# Power_MPU.net
KiCad netlist of a schematic drawn in Altium Designer
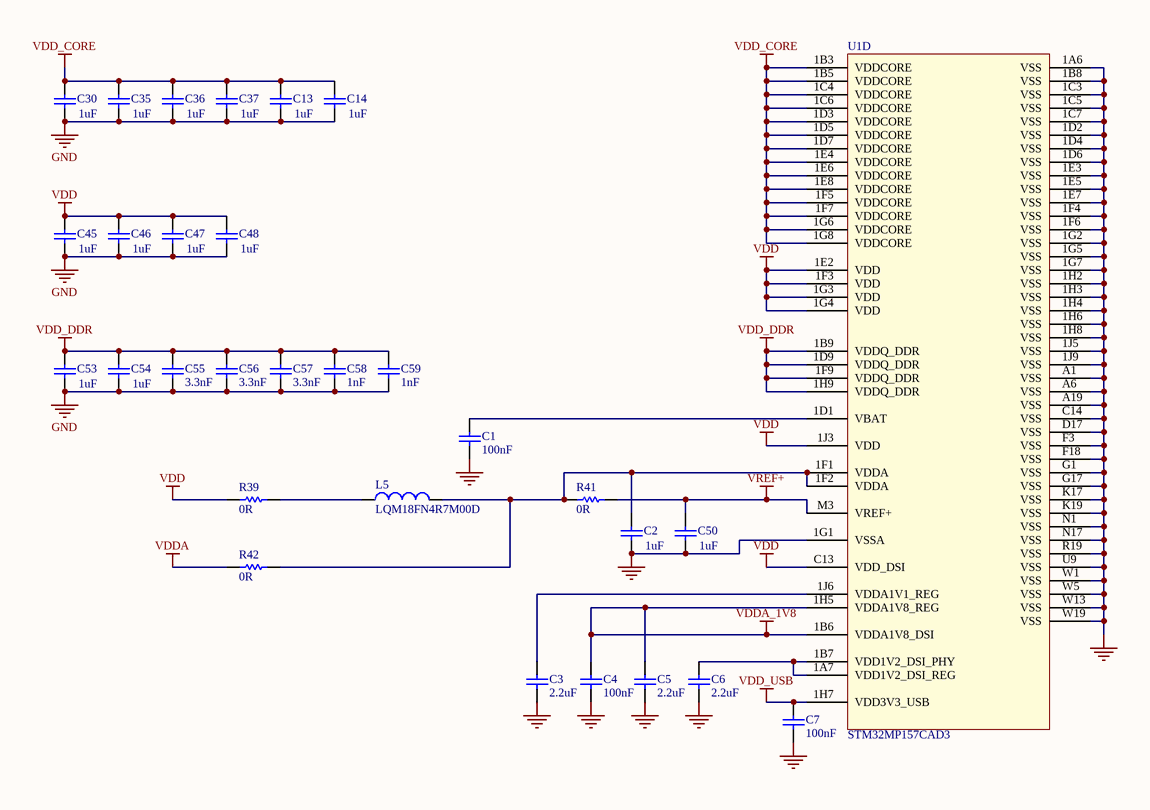
[diagram p0: Power_MPU.SchDoc]

(export (version "E")
  (design (tool "Eeschema 10.0.6"))
  (components
    (comp (ref "C1")
      (value "100nF")
      (footprint "C0402")
      (description "Capacitor, MLCC, 100nF, 16V, X7R, 10%, 0402, T=0.5mm")
      (fields
        (field (name "INTERNAL_PART_NUMBER") "MCD-00006")
        (field (name "MANUFACTURER_PART_NUMBER") "CC0402KRX7R7BB104")
        (field (name "PROVIDED_BY") "SUBCO")
      )
      (libsource (lib "MCD_PARTS_database") (part "Capacitor"))
    )
    (comp (ref "C2")
      (value "1uF")
      (footprint "C0402")
      (description "Capacitor, MLCC, 1uF, 6V3, X5R, 10%, 0402, T=0,5mm")
      (fields
        (field (name "INTERNAL_PART_NUMBER") "MCD-00095")
        (field (name "MANUFACTURER_PART_NUMBER") "GRM155R61E105KA12")
        (field (name "PROVIDED_BY") "SUBCO")
      )
      (libsource (lib "MCD_PARTS_database") (part "Capacitor"))
    )
    (comp (ref "C3")
      (value "2.2uF")
      (footprint "C0402")
      (description "Capacitor,MLCC,2.2uF,6V3,X5R,10%,0402,T=0.5")
      (fields
        (field (name "INTERNAL_PART_NUMBER") "MCD-01823")
        (field (name "MANUFACTURER_PART_NUMBER") "GRM155R60J225KE95D")
        (field (name "PROVIDED_BY") "SUBCO")
      )
      (libsource (lib "MCD_PARTS_database") (part "Capacitor"))
    )
    (comp (ref "C4")
      (value "100nF")
      (footprint "C0402")
      (description "Capacitor, MLCC, 100nF, 16V, X7R, 10%, 0402, T=0.5mm")
      (fields
        (field (name "INTERNAL_PART_NUMBER") "MCD-00006")
        (field (name "MANUFACTURER_PART_NUMBER") "CC0402KRX7R7BB104")
        (field (name "PROVIDED_BY") "SUBCO")
      )
      (libsource (lib "MCD_PARTS_database") (part "Capacitor"))
    )
    (comp (ref "C5")
      (value "2.2uF")
      (footprint "C0402")
      (description "Capacitor,MLCC,2.2uF,6V3,X5R,10%,0402,T=0.5")
      (fields
        (field (name "INTERNAL_PART_NUMBER") "MCD-01823")
        (field (name "MANUFACTURER_PART_NUMBER") "GRM155R60J225KE95D")
        (field (name "PROVIDED_BY") "SUBCO")
      )
      (libsource (lib "MCD_PARTS_database") (part "Capacitor"))
    )
    (comp (ref "C6")
      (value "2.2uF")
      (footprint "C0402")
      (description "Capacitor,MLCC,2.2uF,6V3,X5R,10%,0402,T=0.5")
      (fields
        (field (name "INTERNAL_PART_NUMBER") "MCD-01823")
        (field (name "MANUFACTURER_PART_NUMBER") "GRM155R60J225KE95D")
        (field (name "PROVIDED_BY") "SUBCO")
      )
      (libsource (lib "MCD_PARTS_database") (part "Capacitor"))
    )
    (comp (ref "C7")
      (value "100nF")
      (footprint "C0402")
      (description "Capacitor, MLCC, 100nF, 16V, X7R, 10%, 0402, T=0.5mm")
      (fields
        (field (name "INTERNAL_PART_NUMBER") "MCD-00006")
        (field (name "MANUFACTURER_PART_NUMBER") "CC0402KRX7R7BB104")
        (field (name "PROVIDED_BY") "SUBCO")
      )
      (libsource (lib "MCD_PARTS_database") (part "Capacitor"))
    )
    (comp (ref "C13")
      (value "1uF")
      (footprint "C0402")
      (description "Capacitor, MLCC, 1uF, 6V3, X5R, 10%, 0402, T=0,5mm")
      (fields
        (field (name "INTERNAL_PART_NUMBER") "MCD-00095")
        (field (name "MANUFACTURER_PART_NUMBER") "GRM155R61E105KA12")
        (field (name "PROVIDED_BY") "SUBCO")
      )
      (libsource (lib "MCD_PARTS_database") (part "Capacitor"))
    )
    (comp (ref "C14")
      (value "1uF")
      (footprint "C0402")
      (description "Capacitor, MLCC, 1uF, 6V3, X5R, 10%, 0402, T=0,5mm")
      (fields
        (field (name "INTERNAL_PART_NUMBER") "MCD-00095")
        (field (name "MANUFACTURER_PART_NUMBER") "GRM155R61E105KA12")
        (field (name "PROVIDED_BY") "SUBCO")
      )
      (libsource (lib "MCD_PARTS_database") (part "Capacitor"))
    )
    (comp (ref "C30")
      (value "1uF")
      (footprint "C0402")
      (description "Capacitor, MLCC, 1uF, 6V3, X5R, 10%, 0402, T=0,5mm")
      (fields
        (field (name "INTERNAL_PART_NUMBER") "MCD-00095")
        (field (name "MANUFACTURER_PART_NUMBER") "GRM155R61E105KA12")
        (field (name "PROVIDED_BY") "SUBCO")
      )
      (libsource (lib "MCD_PARTS_database") (part "Capacitor"))
    )
    (comp (ref "C35")
      (value "1uF")
      (footprint "C0402")
      (description "Capacitor, MLCC, 1uF, 6V3, X5R, 10%, 0402, T=0,5mm")
      (fields
        (field (name "INTERNAL_PART_NUMBER") "MCD-00095")
        (field (name "MANUFACTURER_PART_NUMBER") "GRM155R61E105KA12")
        (field (name "PROVIDED_BY") "SUBCO")
      )
      (libsource (lib "MCD_PARTS_database") (part "Capacitor"))
    )
    (comp (ref "C36")
      (value "1uF")
      (footprint "C0402")
      (description "Capacitor, MLCC, 1uF, 6V3, X5R, 10%, 0402, T=0,5mm")
      (fields
        (field (name "INTERNAL_PART_NUMBER") "MCD-00095")
        (field (name "MANUFACTURER_PART_NUMBER") "GRM155R61E105KA12")
        (field (name "PROVIDED_BY") "SUBCO")
      )
      (libsource (lib "MCD_PARTS_database") (part "Capacitor"))
    )
    (comp (ref "C37")
      (value "1uF")
      (footprint "C0402")
      (description "Capacitor, MLCC, 1uF, 6V3, X5R, 10%, 0402, T=0,5mm")
      (fields
        (field (name "INTERNAL_PART_NUMBER") "MCD-00095")
        (field (name "MANUFACTURER_PART_NUMBER") "GRM155R61E105KA12")
        (field (name "PROVIDED_BY") "SUBCO")
      )
      (libsource (lib "MCD_PARTS_database") (part "Capacitor"))
    )
    (comp (ref "C45")
      (value "1uF")
      (footprint "C0402")
      (description "Capacitor, MLCC, 1uF, 6V3, X5R, 10%, 0402, T=0,5mm")
      (fields
        (field (name "INTERNAL_PART_NUMBER") "MCD-00095")
        (field (name "MANUFACTURER_PART_NUMBER") "GRM155R61E105KA12")
        (field (name "PROVIDED_BY") "SUBCO")
      )
      (libsource (lib "MCD_PARTS_database") (part "Capacitor"))
    )
    (comp (ref "C46")
      (value "1uF")
      (footprint "C0402")
      (description "Capacitor, MLCC, 1uF, 6V3, X5R, 10%, 0402, T=0,5mm")
      (fields
        (field (name "INTERNAL_PART_NUMBER") "MCD-00095")
        (field (name "MANUFACTURER_PART_NUMBER") "GRM155R61E105KA12")
        (field (name "PROVIDED_BY") "SUBCO")
      )
      (libsource (lib "MCD_PARTS_database") (part "Capacitor"))
    )
    (comp (ref "C47")
      (value "1uF")
      (footprint "C0402")
      (description "Capacitor, MLCC, 1uF, 6V3, X5R, 10%, 0402, T=0,5mm")
      (fields
        (field (name "INTERNAL_PART_NUMBER") "MCD-00095")
        (field (name "MANUFACTURER_PART_NUMBER") "GRM155R61E105KA12")
        (field (name "PROVIDED_BY") "SUBCO")
      )
      (libsource (lib "MCD_PARTS_database") (part "Capacitor"))
    )
    (comp (ref "C48")
      (value "1uF")
      (footprint "C0402")
      (description "Capacitor, MLCC, 1uF, 6V3, X5R, 10%, 0402, T=0,5mm")
      (fields
        (field (name "INTERNAL_PART_NUMBER") "MCD-00095")
        (field (name "MANUFACTURER_PART_NUMBER") "GRM155R61E105KA12")
        (field (name "PROVIDED_BY") "SUBCO")
      )
      (libsource (lib "MCD_PARTS_database") (part "Capacitor"))
    )
    (comp (ref "C50")
      (value "1uF")
      (footprint "C0402")
      (description "Capacitor, MLCC, 1uF, 6V3, X5R, 10%, 0402, T=0,5mm")
      (fields
        (field (name "INTERNAL_PART_NUMBER") "MCD-00095")
        (field (name "MANUFACTURER_PART_NUMBER") "GRM155R61E105KA12")
        (field (name "PROVIDED_BY") "SUBCO")
      )
      (libsource (lib "MCD_PARTS_database") (part "Capacitor"))
    )
    (comp (ref "C53")
      (value "1uF")
      (footprint "C0402")
      (description "Capacitor, MLCC, 1uF, 6V3, X5R, 10%, 0402, T=0,5mm")
      (fields
        (field (name "INTERNAL_PART_NUMBER") "MCD-00095")
        (field (name "MANUFACTURER_PART_NUMBER") "GRM155R61E105KA12")
        (field (name "PROVIDED_BY") "SUBCO")
      )
      (libsource (lib "MCD_PARTS_database") (part "Capacitor"))
    )
    (comp (ref "C54")
      (value "1uF")
      (footprint "C0402")
      (description "Capacitor, MLCC, 1uF, 6V3, X5R, 10%, 0402, T=0,5mm")
      (fields
        (field (name "INTERNAL_PART_NUMBER") "MCD-00095")
        (field (name "MANUFACTURER_PART_NUMBER") "GRM155R61E105KA12")
        (field (name "PROVIDED_BY") "SUBCO")
      )
      (libsource (lib "MCD_PARTS_database") (part "Capacitor"))
    )
    (comp (ref "C55")
      (value "3.3nF")
      (footprint "C0402")
      (description "Capacitor, MLCC, 3.3nF, 16V, X7R, 10%, 0402, T=0.5mm")
      (fields
        (field (name "INTERNAL_PART_NUMBER") "MCD-01462")
        (field (name "MANUFACTURER_PART_NUMBER") "CC0402KRX7R7BB332")
        (field (name "PROVIDED_BY") "SUBCO")
      )
      (libsource (lib "MCD_PARTS_database") (part "Capacitor"))
    )
    (comp (ref "C56")
      (value "3.3nF")
      (footprint "C0402")
      (description "Capacitor, MLCC, 3.3nF, 16V, X7R, 10%, 0402, T=0.5mm")
      (fields
        (field (name "INTERNAL_PART_NUMBER") "MCD-01462")
        (field (name "MANUFACTURER_PART_NUMBER") "CC0402KRX7R7BB332")
        (field (name "PROVIDED_BY") "SUBCO")
      )
      (libsource (lib "MCD_PARTS_database") (part "Capacitor"))
    )
    (comp (ref "C57")
      (value "3.3nF")
      (footprint "C0402")
      (description "Capacitor, MLCC, 3.3nF, 16V, X7R, 10%, 0402, T=0.5mm")
      (fields
        (field (name "INTERNAL_PART_NUMBER") "MCD-01462")
        (field (name "MANUFACTURER_PART_NUMBER") "CC0402KRX7R7BB332")
        (field (name "PROVIDED_BY") "SUBCO")
      )
      (libsource (lib "MCD_PARTS_database") (part "Capacitor"))
    )
    (comp (ref "C58")
      (value "1nF")
      (footprint "C0402")
      (description "Capacitor, MLCC, 1nF, 16V, X7R, 10%, 0402, T=0.5mm")
      (fields
        (field (name "INTERNAL_PART_NUMBER") "MCD-00198")
        (field (name "MANUFACTURER_PART_NUMBER") "CC0402KRX7R7BB102")
        (field (name "PROVIDED_BY") "SUBCO")
      )
      (libsource (lib "MCD_PARTS_database") (part "Capacitor"))
    )
    (comp (ref "C59")
      (value "1nF")
      (footprint "C0402")
      (description "Capacitor, MLCC, 1nF, 16V, X7R, 10%, 0402, T=0.5mm")
      (fields
        (field (name "INTERNAL_PART_NUMBER") "MCD-00198")
        (field (name "MANUFACTURER_PART_NUMBER") "CC0402KRX7R7BB102")
        (field (name "PROVIDED_BY") "SUBCO")
      )
      (libsource (lib "MCD_PARTS_database") (part "Capacitor"))
    )
    (comp (ref "L5")
      (value "LQM18FN4R7M00D")
      (footprint "L0603_H0P8")
      (description "IND 4.7uH 20% 80mA 600mhom 0603")
      (fields
        (field (name "INTERNAL_PART_NUMBER") "MCD-01134")
        (field (name "MANUFACTURER") "MURATA")
        (field (name "PROVIDED_BY") "SUBCO")
      )
      (libsource (lib "MCD_PARTS_database") (part "LQM18FN4R7M00D"))
    )
    (comp (ref "R39")
      (value "0R")
      (footprint "R0402")
      (description "Resistor,0R,0402,5%,1/16W")
      (fields
        (field (name "INTERNAL_PART_NUMBER") "MCD-00052")
        (field (name "MANUFACTURER_PART_NUMBER") "RC0402JR-070RL")
        (field (name "PROVIDED_BY") "SUBCO")
      )
      (libsource (lib "MCD_PARTS_database") (part "Resistor"))
    )
    (comp (ref "R41")
      (value "0R")
      (footprint "R0402")
      (description "Resistor,0R,0402,5%,1/16W")
      (fields
        (field (name "INTERNAL_PART_NUMBER") "MCD-00052")
        (field (name "MANUFACTURER_PART_NUMBER") "RC0402JR-070RL")
        (field (name "PROVIDED_BY") "SUBCO")
      )
      (libsource (lib "MCD_PARTS_database") (part "Resistor"))
    )
    (comp (ref "R42")
      (value "0R")
      (footprint "R0402")
      (description "Resistor,0R,0402,5%,1/16W")
      (fields
        (field (name "INTERNAL_PART_NUMBER") "MCD-00052")
        (field (name "MANUFACTURER_PART_NUMBER") "RC0402JR-070RL")
        (field (name "PROVIDED_BY") "SUBCO")
      )
      (libsource (lib "MCD_PARTS_database") (part "Resistor"))
    )
    (comp (ref "U1")
      (value "STM32MP157CAD3")
      (footprint "ICC_TFBGA257_10X10_STM32MP157CAD3_P050-065")
      (description "MPU TFBGA10x10 secure boot+crypto")
      (fields
        (field (name "INTERNAL_PART_NUMBER") "MCD-01144")
        (field (name "MANUFACTURER") "STMICROELECTRONICS")
        (field (name "PROVIDED_BY") "SUBCO with ST control")
      )
      (libsource (lib "MCD_PARTS_database") (part "STM32MP157CAD3"))
    )
  )
  (nets
    (net (code "1") (name "GND") (class "Default")
      (node (ref "C1") (pin "1") (pinfunction "1_1") (pintype "passive"))
      (node (ref "C13") (pin "1") (pinfunction "1_1") (pintype "passive"))
      (node (ref "C14") (pin "1") (pinfunction "1_1") (pintype "passive"))
      (node (ref "C2") (pin "1") (pinfunction "1_1") (pintype "passive"))
      (node (ref "C3") (pin "1") (pinfunction "1_1") (pintype "passive"))
      (node (ref "C30") (pin "1") (pinfunction "1_1") (pintype "passive"))
      (node (ref "C35") (pin "1") (pinfunction "1_1") (pintype "passive"))
      (node (ref "C36") (pin "1") (pinfunction "1_1") (pintype "passive"))
      (node (ref "C37") (pin "1") (pinfunction "1_1") (pintype "passive"))
      (node (ref "C4") (pin "1") (pinfunction "1_1") (pintype "passive"))
      (node (ref "C45") (pin "1") (pinfunction "1_1") (pintype "passive"))
      (node (ref "C46") (pin "1") (pinfunction "1_1") (pintype "passive"))
      (node (ref "C47") (pin "1") (pinfunction "1_1") (pintype "passive"))
      (node (ref "C48") (pin "1") (pinfunction "1_1") (pintype "passive"))
      (node (ref "C5") (pin "1") (pinfunction "1_1") (pintype "passive"))
      (node (ref "C50") (pin "1") (pinfunction "1_1") (pintype "passive"))
      (node (ref "C53") (pin "1") (pinfunction "1_1") (pintype "passive"))
      (node (ref "C54") (pin "1") (pinfunction "1_1") (pintype "passive"))
      (node (ref "C55") (pin "1") (pinfunction "1_1") (pintype "passive"))
      (node (ref "C56") (pin "1") (pinfunction "1_1") (pintype "passive"))
      (node (ref "C57") (pin "1") (pinfunction "1_1") (pintype "passive"))
      (node (ref "C58") (pin "1") (pinfunction "1_1") (pintype "passive"))
      (node (ref "C59") (pin "1") (pinfunction "1_1") (pintype "passive"))
      (node (ref "C6") (pin "1") (pinfunction "1_1") (pintype "passive"))
      (node (ref "C7") (pin "1") (pinfunction "1_1") (pintype "passive"))
      (node (ref "U1") (pin "1A6") (pinfunction "VSS_1A6") (pintype "passive"))
      (node (ref "U1") (pin "1B8") (pinfunction "VSS_1B8") (pintype "passive"))
      (node (ref "U1") (pin "1C3") (pinfunction "VSS_1C3") (pintype "passive"))
      (node (ref "U1") (pin "1C5") (pinfunction "VSS_1C5") (pintype "passive"))
      (node (ref "U1") (pin "1C7") (pinfunction "VSS_1C7") (pintype "passive"))
      (node (ref "U1") (pin "1D2") (pinfunction "VSS_1D2") (pintype "passive"))
      (node (ref "U1") (pin "1D4") (pinfunction "VSS_1D4") (pintype "passive"))
      (node (ref "U1") (pin "1D6") (pinfunction "VSS_1D6") (pintype "passive"))
      (node (ref "U1") (pin "1E3") (pinfunction "VSS_1E3") (pintype "passive"))
      (node (ref "U1") (pin "1E5") (pinfunction "VSS_1E5") (pintype "passive"))
      (node (ref "U1") (pin "1E7") (pinfunction "VSS_1E7") (pintype "passive"))
      (node (ref "U1") (pin "1F4") (pinfunction "VSS_1F4") (pintype "passive"))
      (node (ref "U1") (pin "1F6") (pinfunction "VSS_1F6") (pintype "passive"))
      (node (ref "U1") (pin "1G1") (pinfunction "VSSA_1G1") (pintype "passive"))
      (node (ref "U1") (pin "1G2") (pinfunction "VSS_1G2") (pintype "passive"))
      (node (ref "U1") (pin "1G5") (pinfunction "VSS_1G5") (pintype "passive"))
      (node (ref "U1") (pin "1G7") (pinfunction "VSS_1G7") (pintype "passive"))
      (node (ref "U1") (pin "1H2") (pinfunction "VSS_1H2") (pintype "passive"))
      (node (ref "U1") (pin "1H3") (pinfunction "VSS_1H3") (pintype "passive"))
      (node (ref "U1") (pin "1H4") (pinfunction "VSS_1H4") (pintype "passive"))
      (node (ref "U1") (pin "1H6") (pinfunction "VSS_1H6") (pintype "passive"))
      (node (ref "U1") (pin "1H8") (pinfunction "VSS_1H8") (pintype "passive"))
      (node (ref "U1") (pin "1J5") (pinfunction "VSS_1J5") (pintype "passive"))
      (node (ref "U1") (pin "1J9") (pinfunction "VSS_1J9") (pintype "passive"))
      (node (ref "U1") (pin "A1") (pinfunction "VSS_A1") (pintype "passive"))
      (node (ref "U1") (pin "A19") (pinfunction "VSS_A19") (pintype "passive"))
      (node (ref "U1") (pin "A6") (pinfunction "VSS_A6") (pintype "passive"))
      (node (ref "U1") (pin "C14") (pinfunction "VSS_C14") (pintype "passive"))
      (node (ref "U1") (pin "D17") (pinfunction "VSS_D17") (pintype "passive"))
      (node (ref "U1") (pin "F18") (pinfunction "VSS_F18") (pintype "passive"))
      (node (ref "U1") (pin "F3") (pinfunction "VSS_F3") (pintype "passive"))
      (node (ref "U1") (pin "G1") (pinfunction "VSS_G1") (pintype "passive"))
      (node (ref "U1") (pin "G17") (pinfunction "VSS_G17") (pintype "passive"))
      (node (ref "U1") (pin "K17") (pinfunction "VSS_K17") (pintype "passive"))
      (node (ref "U1") (pin "K19") (pinfunction "VSS_K19") (pintype "passive"))
      (node (ref "U1") (pin "N1") (pinfunction "VSS_N1") (pintype "passive"))
      (node (ref "U1") (pin "N17") (pinfunction "VSS_N17") (pintype "passive"))
      (node (ref "U1") (pin "R19") (pinfunction "VSS_R19") (pintype "passive"))
      (node (ref "U1") (pin "U9") (pinfunction "VSS_U9") (pintype "passive"))
      (node (ref "U1") (pin "W1") (pinfunction "VSS_W1") (pintype "passive"))
      (node (ref "U1") (pin "W13") (pinfunction "VSS_W13") (pintype "passive"))
      (node (ref "U1") (pin "W19") (pinfunction "VSS_W19") (pintype "passive"))
      (node (ref "U1") (pin "W5") (pinfunction "VSS_W5") (pintype "passive"))
    )
    (net (code "2") (name "Net-(C2-Pad2)") (class "Default")
      (node (ref "C2") (pin "2") (pinfunction "2_2") (pintype "passive"))
      (node (ref "L5") (pin "2") (pinfunction "2_2") (pintype "passive"))
      (node (ref "R41") (pin "1") (pinfunction "1_1") (pintype "passive"))
      (node (ref "R42") (pin "2") (pinfunction "2_2") (pintype "passive"))
      (node (ref "U1") (pin "1F1") (pinfunction "VDDA_1F1") (pintype "passive"))
      (node (ref "U1") (pin "1F2") (pinfunction "VDDA_1F2") (pintype "passive"))
    )
    (net (code "3") (name "Net-(L5-Pad1)") (class "Default")
      (node (ref "L5") (pin "1") (pinfunction "1_1") (pintype "passive"))
      (node (ref "R39") (pin "2") (pinfunction "2_2") (pintype "passive"))
    )
    (net (code "4") (name "Net-(U1D-VBAT)") (class "Default")
      (node (ref "C1") (pin "2") (pinfunction "2_2") (pintype "passive"))
      (node (ref "U1") (pin "1D1") (pinfunction "VBAT_1D1") (pintype "passive"))
    )
    (net (code "5") (name "Net-(U1D-VDD1V2_DSI_PHY)") (class "Default")
      (node (ref "C6") (pin "2") (pinfunction "2_2") (pintype "passive"))
      (node (ref "U1") (pin "1A7") (pinfunction "VDD1V2_DSI_REG_1A7") (pintype "passive"))
      (node (ref "U1") (pin "1B7") (pinfunction "VDD1V2_DSI_PHY_1B7") (pintype "passive"))
    )
    (net (code "6") (name "Net-(U1D-VDDA1V1_REG)") (class "Default")
      (node (ref "C3") (pin "2") (pinfunction "2_2") (pintype "passive"))
      (node (ref "U1") (pin "1J6") (pinfunction "VDDA1V1_REG_1J6") (pintype "passive"))
    )
    (net (code "7") (name "VDD") (class "Default")
      (node (ref "C45") (pin "2") (pinfunction "2_2") (pintype "passive"))
      (node (ref "C46") (pin "2") (pinfunction "2_2") (pintype "passive"))
      (node (ref "C47") (pin "2") (pinfunction "2_2") (pintype "passive"))
      (node (ref "C48") (pin "2") (pinfunction "2_2") (pintype "passive"))
      (node (ref "R39") (pin "1") (pinfunction "1_1") (pintype "passive"))
      (node (ref "U1") (pin "1E2") (pinfunction "VDD_1E2") (pintype "passive"))
      (node (ref "U1") (pin "1F3") (pinfunction "VDD_1F3") (pintype "passive"))
      (node (ref "U1") (pin "1G3") (pinfunction "VDD_1G3") (pintype "passive"))
      (node (ref "U1") (pin "1G4") (pinfunction "VDD_1G4") (pintype "passive"))
      (node (ref "U1") (pin "1J3") (pinfunction "VDD_1J3") (pintype "passive"))
      (node (ref "U1") (pin "C13") (pinfunction "VDD_DSI_C13") (pintype "passive"))
    )
    (net (code "8") (name "VDDA") (class "Default")
      (node (ref "R42") (pin "1") (pinfunction "1_1") (pintype "passive"))
    )
    (net (code "9") (name "VDDA_1V8") (class "Default")
      (node (ref "C4") (pin "2") (pinfunction "2_2") (pintype "passive"))
      (node (ref "C5") (pin "2") (pinfunction "2_2") (pintype "passive"))
      (node (ref "U1") (pin "1B6") (pinfunction "VDDA1V8_DSI_1B6") (pintype "passive"))
      (node (ref "U1") (pin "1H5") (pinfunction "VDDA1V8_REG_1H5") (pintype "passive"))
    )
    (net (code "10") (name "VDD_CORE") (class "Default")
      (node (ref "C13") (pin "2") (pinfunction "2_2") (pintype "passive"))
      (node (ref "C14") (pin "2") (pinfunction "2_2") (pintype "passive"))
      (node (ref "C30") (pin "2") (pinfunction "2_2") (pintype "passive"))
      (node (ref "C35") (pin "2") (pinfunction "2_2") (pintype "passive"))
      (node (ref "C36") (pin "2") (pinfunction "2_2") (pintype "passive"))
      (node (ref "C37") (pin "2") (pinfunction "2_2") (pintype "passive"))
      (node (ref "U1") (pin "1B3") (pinfunction "VDDCORE_1B3") (pintype "passive"))
      (node (ref "U1") (pin "1B5") (pinfunction "VDDCORE_1B5") (pintype "passive"))
      (node (ref "U1") (pin "1C4") (pinfunction "VDDCORE_1C4") (pintype "passive"))
      (node (ref "U1") (pin "1C6") (pinfunction "VDDCORE_1C6") (pintype "passive"))
      (node (ref "U1") (pin "1D3") (pinfunction "VDDCORE_1D3") (pintype "passive"))
      (node (ref "U1") (pin "1D5") (pinfunction "VDDCORE_1D5") (pintype "passive"))
      (node (ref "U1") (pin "1D7") (pinfunction "VDDCORE_1D7") (pintype "passive"))
      (node (ref "U1") (pin "1E4") (pinfunction "VDDCORE_1E4") (pintype "passive"))
      (node (ref "U1") (pin "1E6") (pinfunction "VDDCORE_1E6") (pintype "passive"))
      (node (ref "U1") (pin "1E8") (pinfunction "VDDCORE_1E8") (pintype "passive"))
      (node (ref "U1") (pin "1F5") (pinfunction "VDDCORE_1F5") (pintype "passive"))
      (node (ref "U1") (pin "1F7") (pinfunction "VDDCORE_1F7") (pintype "passive"))
      (node (ref "U1") (pin "1G6") (pinfunction "VDDCORE_1G6") (pintype "passive"))
      (node (ref "U1") (pin "1G8") (pinfunction "VDDCORE_1G8") (pintype "passive"))
    )
    (net (code "11") (name "VDD_DDR") (class "Default")
      (node (ref "C53") (pin "2") (pinfunction "2_2") (pintype "passive"))
      (node (ref "C54") (pin "2") (pinfunction "2_2") (pintype "passive"))
      (node (ref "C55") (pin "2") (pinfunction "2_2") (pintype "passive"))
      (node (ref "C56") (pin "2") (pinfunction "2_2") (pintype "passive"))
      (node (ref "C57") (pin "2") (pinfunction "2_2") (pintype "passive"))
      (node (ref "C58") (pin "2") (pinfunction "2_2") (pintype "passive"))
      (node (ref "C59") (pin "2") (pinfunction "2_2") (pintype "passive"))
      (node (ref "U1") (pin "1B9") (pinfunction "VDDQ_DDR_1B9") (pintype "passive"))
      (node (ref "U1") (pin "1D9") (pinfunction "VDDQ_DDR_1D9") (pintype "passive"))
      (node (ref "U1") (pin "1F9") (pinfunction "VDDQ_DDR_1F9") (pintype "passive"))
      (node (ref "U1") (pin "1H9") (pinfunction "VDDQ_DDR_1H9") (pintype "passive"))
    )
    (net (code "12") (name "VDD_USB") (class "Default")
      (node (ref "C7") (pin "2") (pinfunction "2_2") (pintype "passive"))
      (node (ref "U1") (pin "1H7") (pinfunction "VDD3V3_USB_1H7") (pintype "passive"))
    )
    (net (code "13") (name "VREF+") (class "Default")
      (node (ref "C50") (pin "2") (pinfunction "2_2") (pintype "passive"))
      (node (ref "R41") (pin "2") (pinfunction "2_2") (pintype "passive"))
      (node (ref "U1") (pin "M3") (pinfunction "VREF+_M3") (pintype "passive"))
    )
  )
)
